# LEDTestingCircuit.net
KiCad netlist of a schematic drawn in EAGLE
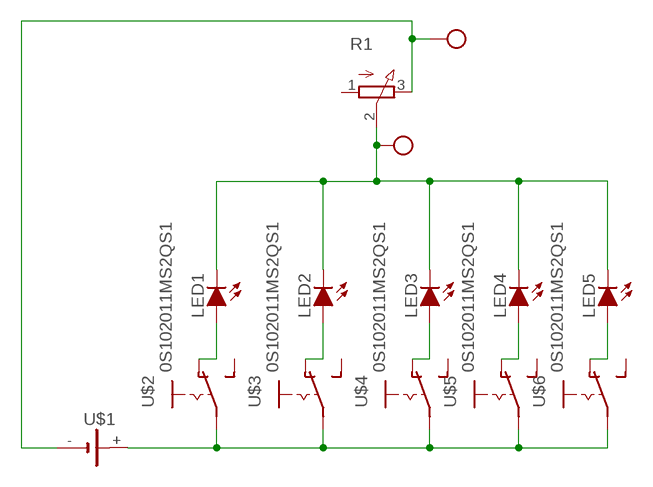
[diagram p0: schematic, sheet 1]

(export (version "E")
  (design (tool "Eeschema 10.0.6"))
  (components
    (comp (ref "LED1")
      (value "LED-0805")
      (footprint "eagle-import:LED-805")
      (libsource (lib "eagle-import") (part "LED-0805"))
    )
    (comp (ref "LED2")
      (value "LED-0805")
      (footprint "eagle-import:LED-805")
      (libsource (lib "eagle-import") (part "LED-0805"))
    )
    (comp (ref "LED3")
      (value "LED-0805")
      (footprint "eagle-import:LED-805")
      (libsource (lib "eagle-import") (part "LED-0805"))
    )
    (comp (ref "LED4")
      (value "LED-0805")
      (footprint "eagle-import:LED-805")
      (libsource (lib "eagle-import") (part "LED-0805"))
    )
    (comp (ref "LED5")
      (value "LED-0805")
      (footprint "eagle-import:LED-805")
      (libsource (lib "eagle-import") (part "LED-0805"))
    )
    (comp (ref "R1")
      (value "3RP/1610N")
      (footprint "eagle-import:3RP_1610N")
      (libsource (lib "eagle-import") (part "3RP/1610N"))
    )
    (comp (ref "U$1")
      (value "1291-79")
      (footprint "eagle-import:1291-79")
      (libsource (lib "eagle-import") (part "1291-79"))
    )
    (comp (ref "U$2")
      (value "0S102011MS2QS1")
      (footprint "eagle-import:0S102011MS2QS1")
      (libsource (lib "eagle-import") (part "0S102011MS2QS1"))
    )
    (comp (ref "U$3")
      (value "0S102011MS2QS1")
      (footprint "eagle-import:0S102011MS2QS1")
      (libsource (lib "eagle-import") (part "0S102011MS2QS1"))
    )
    (comp (ref "U$4")
      (value "0S102011MS2QS1")
      (footprint "eagle-import:0S102011MS2QS1")
      (libsource (lib "eagle-import") (part "0S102011MS2QS1"))
    )
    (comp (ref "U$5")
      (value "0S102011MS2QS1")
      (footprint "eagle-import:0S102011MS2QS1")
      (libsource (lib "eagle-import") (part "0S102011MS2QS1"))
    )
    (comp (ref "U$6")
      (value "0S102011MS2QS1")
      (footprint "eagle-import:0S102011MS2QS1")
      (libsource (lib "eagle-import") (part "0S102011MS2QS1"))
    )
    (comp (ref "U$7")
      (value "TEST_POINT")
      (footprint "eagle-import:TEST_POINT")
      (libsource (lib "eagle-import") (part "TEST_POINT"))
    )
    (comp (ref "U$8")
      (value "TEST_POINT")
      (footprint "eagle-import:TEST_POINT")
      (libsource (lib "eagle-import") (part "TEST_POINT"))
    )
  )
  (nets
    (net (code "1") (name "Net-(R1-E)") (class "Default")
      (node (ref "R1") (pin "3") (pinfunction "E_3") (pintype "passive"))
      (node (ref "U$1") (pin "-") (pinfunction "-_-") (pintype "passive"))
      (node (ref "U$8") (pin "P$1") (pinfunction "P$1_P$1") (pintype "bidirectional"))
    )
    (net (code "2") (name "Net-(R1-S)") (class "Default")
      (node (ref "LED1") (pin "C") (pinfunction "C_C") (pintype "passive"))
      (node (ref "LED2") (pin "C") (pinfunction "C_C") (pintype "passive"))
      (node (ref "LED3") (pin "C") (pinfunction "C_C") (pintype "passive"))
      (node (ref "LED4") (pin "C") (pinfunction "C_C") (pintype "passive"))
      (node (ref "LED5") (pin "C") (pinfunction "C_C") (pintype "passive"))
      (node (ref "R1") (pin "2") (pinfunction "S_2") (pintype "passive"))
      (node (ref "U$7") (pin "P$1") (pinfunction "P$1_P$1") (pintype "bidirectional"))
    )
    (net (code "3") (name "Net-(U$2-O)") (class "Default")
      (node (ref "LED1") (pin "A") (pinfunction "A_A") (pintype "passive"))
      (node (ref "U$2") (pin "P$1") (pinfunction "O_P$1") (pintype "passive"))
    )
    (net (code "4") (name "Net-(U$2-P)") (class "Default")
      (node (ref "U$1") (pin "+") (pinfunction "+_+") (pintype "passive"))
      (node (ref "U$2") (pin "P$2") (pinfunction "P_P$2") (pintype "passive"))
      (node (ref "U$3") (pin "P$2") (pinfunction "P_P$2") (pintype "passive"))
      (node (ref "U$4") (pin "P$2") (pinfunction "P_P$2") (pintype "passive"))
      (node (ref "U$5") (pin "P$2") (pinfunction "P_P$2") (pintype "passive"))
      (node (ref "U$6") (pin "P$2") (pinfunction "P_P$2") (pintype "passive"))
    )
    (net (code "5") (name "Net-(U$3-O)") (class "Default")
      (node (ref "LED2") (pin "A") (pinfunction "A_A") (pintype "passive"))
      (node (ref "U$3") (pin "P$1") (pinfunction "O_P$1") (pintype "passive"))
    )
    (net (code "6") (name "Net-(U$4-O)") (class "Default")
      (node (ref "LED3") (pin "A") (pinfunction "A_A") (pintype "passive"))
      (node (ref "U$4") (pin "P$1") (pinfunction "O_P$1") (pintype "passive"))
    )
    (net (code "7") (name "Net-(U$5-O)") (class "Default")
      (node (ref "LED4") (pin "A") (pinfunction "A_A") (pintype "passive"))
      (node (ref "U$5") (pin "P$1") (pinfunction "O_P$1") (pintype "passive"))
    )
    (net (code "8") (name "Net-(U$6-O)") (class "Default")
      (node (ref "LED5") (pin "A") (pinfunction "A_A") (pintype "passive"))
      (node (ref "U$6") (pin "P$1") (pinfunction "O_P$1") (pintype "passive"))
    )
    (net (code "9") (name "unconnected-(R1-A-Pad1)") (class "Default")
      (node (ref "R1") (pin "1") (pinfunction "A_1") (pintype "passive"))
    )
    (net (code "10") (name "unconnected-(U$2-S-PadP$3)") (class "Default")
      (node (ref "U$2") (pin "P$3") (pinfunction "S_P$3") (pintype "passive"))
    )
    (net (code "11") (name "unconnected-(U$3-S-PadP$3)") (class "Default")
      (node (ref "U$3") (pin "P$3") (pinfunction "S_P$3") (pintype "passive"))
    )
    (net (code "12") (name "unconnected-(U$4-S-PadP$3)") (class "Default")
      (node (ref "U$4") (pin "P$3") (pinfunction "S_P$3") (pintype "passive"))
    )
    (net (code "13") (name "unconnected-(U$5-S-PadP$3)") (class "Default")
      (node (ref "U$5") (pin "P$3") (pinfunction "S_P$3") (pintype "passive"))
    )
    (net (code "14") (name "unconnected-(U$6-S-PadP$3)") (class "Default")
      (node (ref "U$6") (pin "P$3") (pinfunction "S_P$3") (pintype "passive"))
    )
  )
)
